# bike_light2.net
KiCad netlist of a schematic drawn in EAGLE
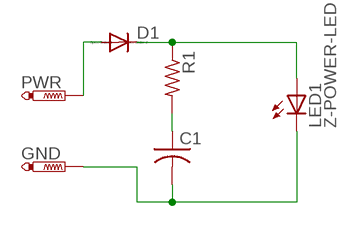
[diagram p0: schematic, sheet 1]

(export (version "E")
  (design (tool "Eeschema 10.0.6"))
  (components
    (comp (ref "C1")
      (value "SUPERCAP5.5_1FDGH")
      (footprint "eagle-import:CAP_1UF_DGH")
      (libsource (lib "eagle-import") (part "SUPERCAP5.5_1FDGH"))
    )
    (comp (ref "D1")
      (value "DIODE-DO-214AC")
      (footprint "eagle-import:DO-214AC")
      (libsource (lib "eagle-import") (part "DIODE-DO-214AC"))
    )
    (comp (ref "GND")
      (value "PTR1PAD1-13Y")
      (footprint "eagle-import:P1-13Y")
      (libsource (lib "eagle-import") (part "PTR1PAD1-13Y"))
    )
    (comp (ref "LED1")
      (value "Z-POWER-LED")
      (footprint "eagle-import:Z-POWER-LED-PCB-TYPE")
      (libsource (lib "eagle-import") (part "Z-POWER-LED"))
    )
    (comp (ref "PWR")
      (value "PTR1PAD1-13Y")
      (footprint "eagle-import:P1-13Y")
      (libsource (lib "eagle-import") (part "PTR1PAD1-13Y"))
    )
    (comp (ref "R1")
      (value "R-US_M1206")
      (footprint "eagle-import:M1206")
      (libsource (lib "eagle-import") (part "R-US_M1206"))
    )
  )
  (nets
    (net (code "1") (name "Net-(C1-1)") (class "Default")
      (node (ref "C1") (pin "P$1") (pinfunction "1_P$1") (pintype "passive"))
      (node (ref "R1") (pin "2") (pinfunction "2_2") (pintype "passive"))
    )
    (net (code "2") (name "Net-(C1-2)") (class "Default")
      (node (ref "C1") (pin "P$2") (pinfunction "2_P$2") (pintype "passive"))
      (node (ref "GND") (pin "TP") (pinfunction "TP_TP") (pintype "input"))
      (node (ref "LED1") (pin "C") (pinfunction "C_C") (pintype "passive"))
    )
    (net (code "3") (name "Net-(D1-PadA)") (class "Default")
      (node (ref "D1") (pin "A") (pinfunction "A_A") (pintype "passive"))
      (node (ref "PWR") (pin "TP") (pinfunction "TP_TP") (pintype "input"))
    )
    (net (code "4") (name "Net-(D1-PadC)") (class "Default")
      (node (ref "D1") (pin "C") (pinfunction "C_C") (pintype "passive"))
      (node (ref "LED1") (pin "A") (pinfunction "A_A") (pintype "passive"))
      (node (ref "R1") (pin "1") (pinfunction "1_1") (pintype "passive"))
    )
  )
)
